# H-00488_-_Top.net
KiCad netlist of a schematic drawn in Altium Designer
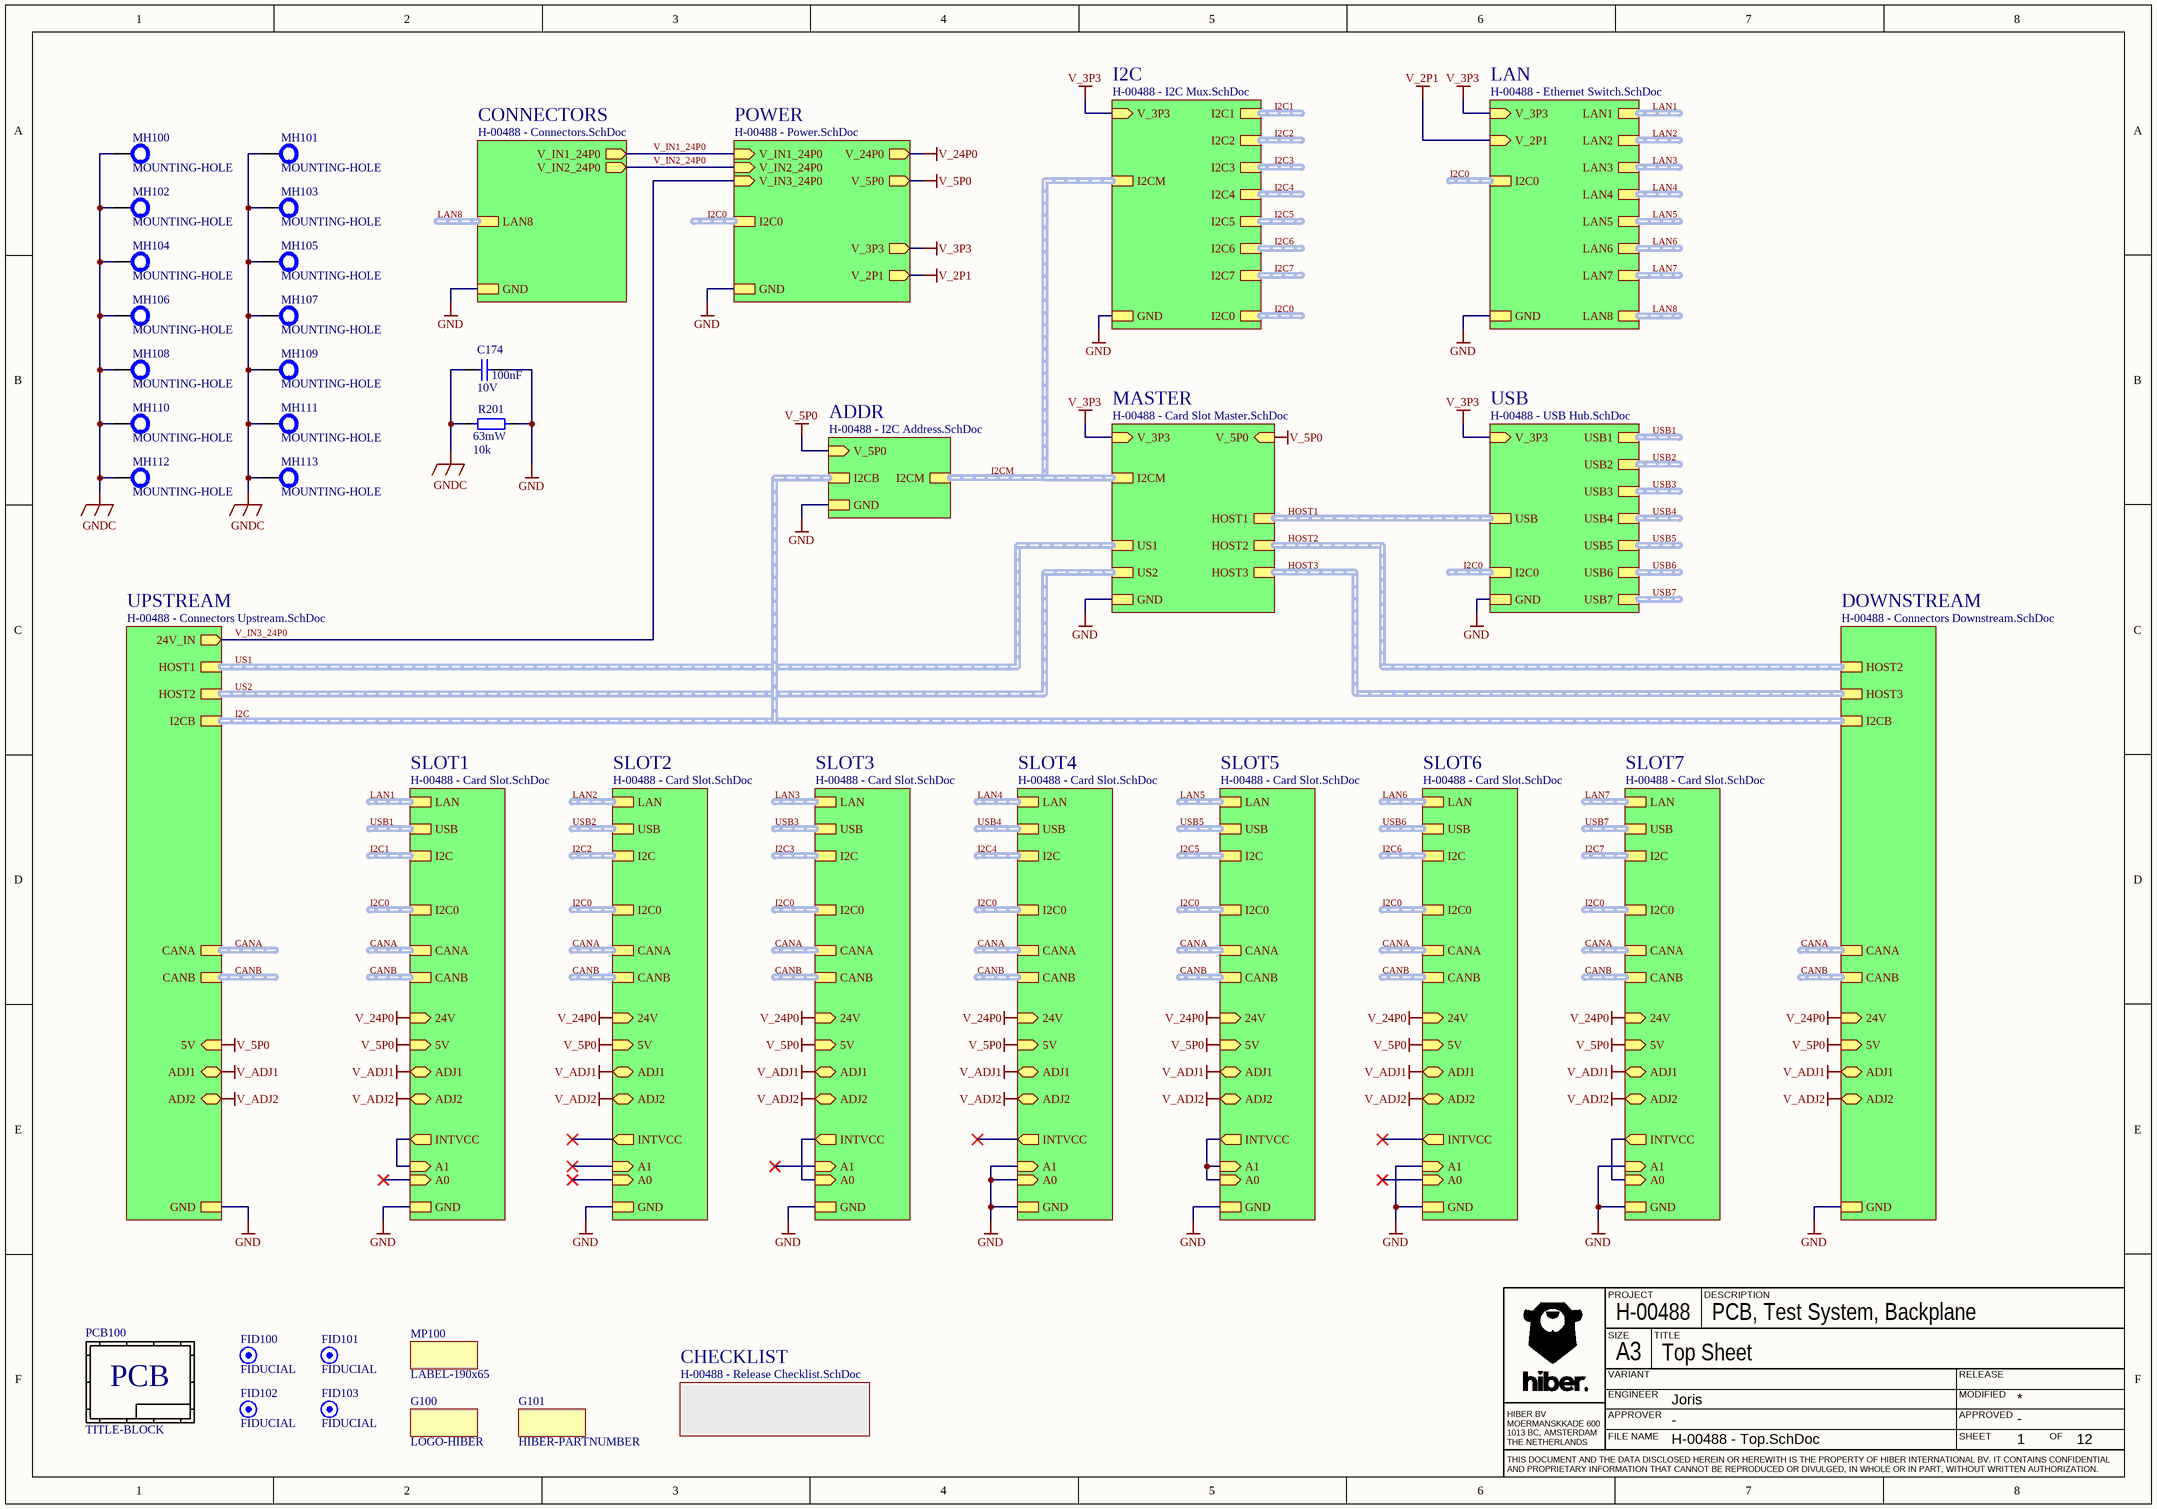
[diagram p0: H-00488 - Top.SchDoc]

(export (version "E")
  (design (tool "Eeschema 10.0.6"))
  (components
    (comp (ref "C174")
      (value "100nF")
      (footprint "CAPC100X50X55L30N")
      (description "CAP Standard 0402 (1005) 100,0nF 10V X7R (Standard)")
      (fields
        (field (name "RATED VOLTAGE") "10V")
        (field (name "TOLERANCE") "10%")
        (field (name "Comment") "C0402C104K8RACTU")
      )
      (libsource (lib "Hiber Vault") (part "CAPACITOR"))
    )
    (comp (ref "FID100")
      (value "FIDUCIAL")
      (footprint "FIDUCIAL_075X150")
      (description "Fiducial")
      (libsource (lib "Hiber Vault") (part "FIDUCIAL"))
    )
    (comp (ref "FID101")
      (value "FIDUCIAL")
      (footprint "FIDUCIAL_075X150")
      (description "Fiducial")
      (libsource (lib "Hiber Vault") (part "FIDUCIAL"))
    )
    (comp (ref "FID102")
      (value "FIDUCIAL")
      (footprint "FIDUCIAL_075X150")
      (description "Fiducial")
      (libsource (lib "Hiber Vault") (part "FIDUCIAL"))
    )
    (comp (ref "FID103")
      (value "FIDUCIAL")
      (footprint "FIDUCIAL_075X150")
      (description "Fiducial")
      (libsource (lib "Hiber Vault") (part "FIDUCIAL"))
    )
    (comp (ref "G100")
      (value "LOGO-HIBER")
      (footprint "HIBER_LOGO_COPPER_55x40")
      (description "Hiber Logo")
      (libsource (lib "Hiber Vault") (part "GRAPHIC"))
    )
    (comp (ref "G101")
      (value "HIBER-PARTNUMBER")
      (footprint "HIBER_PNSN_COPPER")
      (description "Hiber Fabrication Partnumber")
      (libsource (lib "Hiber") (part "GRAPHIC"))
    )
    (comp (ref "MH100")
      (value "MOUNTING-HOLE")
      (footprint "MTGP510H260V8H25")
      (description "Mounting Hole")
      (libsource (lib "Hiber Vault") (part "MOUNTING-HOLE-PLATED"))
    )
    (comp (ref "MH101")
      (value "MOUNTING-HOLE")
      (footprint "MTGP510H260V8H25")
      (description "Mounting Hole")
      (libsource (lib "Hiber Vault") (part "MOUNTING-HOLE-PLATED"))
    )
    (comp (ref "MH102")
      (value "MOUNTING-HOLE")
      (footprint "MTGP510H260V8H25")
      (description "Mounting Hole")
      (libsource (lib "Hiber Vault") (part "MOUNTING-HOLE-PLATED"))
    )
    (comp (ref "MH103")
      (value "MOUNTING-HOLE")
      (footprint "MTGP510H260V8H25")
      (description "Mounting Hole")
      (libsource (lib "Hiber Vault") (part "MOUNTING-HOLE-PLATED"))
    )
    (comp (ref "MH104")
      (value "MOUNTING-HOLE")
      (footprint "MTGP510H260V8H25")
      (description "Mounting Hole")
      (libsource (lib "Hiber Vault") (part "MOUNTING-HOLE-PLATED"))
    )
    (comp (ref "MH105")
      (value "MOUNTING-HOLE")
      (footprint "MTGP510H260V8H25")
      (description "Mounting Hole")
      (libsource (lib "Hiber Vault") (part "MOUNTING-HOLE-PLATED"))
    )
    (comp (ref "MH106")
      (value "MOUNTING-HOLE")
      (footprint "MTGP510H260V8H25")
      (description "Mounting Hole")
      (libsource (lib "Hiber Vault") (part "MOUNTING-HOLE-PLATED"))
    )
    (comp (ref "MH107")
      (value "MOUNTING-HOLE")
      (footprint "MTGP510H260V8H25")
      (description "Mounting Hole")
      (libsource (lib "Hiber Vault") (part "MOUNTING-HOLE-PLATED"))
    )
    (comp (ref "MH108")
      (value "MOUNTING-HOLE")
      (footprint "MTGP510H260V8H25")
      (description "Mounting Hole")
      (libsource (lib "Hiber Vault") (part "MOUNTING-HOLE-PLATED"))
    )
    (comp (ref "MH109")
      (value "MOUNTING-HOLE")
      (footprint "MTGP510H260V8H25")
      (description "Mounting Hole")
      (libsource (lib "Hiber Vault") (part "MOUNTING-HOLE-PLATED"))
    )
    (comp (ref "MH110")
      (value "MOUNTING-HOLE")
      (footprint "MTGP510H260V8H25")
      (description "Mounting Hole")
      (libsource (lib "Hiber Vault") (part "MOUNTING-HOLE-PLATED"))
    )
    (comp (ref "MH111")
      (value "MOUNTING-HOLE")
      (footprint "MTGP510H260V8H25")
      (description "Mounting Hole")
      (libsource (lib "Hiber Vault") (part "MOUNTING-HOLE-PLATED"))
    )
    (comp (ref "MH112")
      (value "MOUNTING-HOLE")
      (footprint "MTGP510H260V8H25")
      (description "Mounting Hole")
      (libsource (lib "Hiber Vault") (part "MOUNTING-HOLE-PLATED"))
    )
    (comp (ref "MH113")
      (value "MOUNTING-HOLE")
      (footprint "MTGP510H260V8H25")
      (description "Mounting Hole")
      (libsource (lib "Hiber Vault") (part "MOUNTING-HOLE-PLATED"))
    )
    (comp (ref "MP100")
      (value "LABEL-190x65")
      (footprint "LABEL_200X65_OVERLAY")
      (description "Label Placeholder 0.75\" x 0.25\" (Zebra 10015764)")
      (libsource (lib "Hiber") (part "MECHANICAL-PART"))
    )
    (comp (ref "PCB100")
      (value "TITLE-BLOCK")
      (footprint "TITLEBLOCK-A4")
      (description "Title Block and PCB BOM Line Item")
      (libsource (lib "Hiber") (part "TITLE-BLOCK"))
    )
    (comp (ref "R201")
      (value "10k")
      (footprint "RESC100X50X40L25N")
      (description "RES Standard Thick Film 0402 10K0 ±1% 0,063W")
      (fields
        (field (name "TOLERANCE") "1%")
        (field (name "RATED POWER") "63mW")
        (field (name "Comment") "CRCW040210K0FKED")
      )
      (libsource (lib "Hiber") (part "RESISTOR-2P"))
    )
  )
  (nets
    (net (code "80") (name "GND") (class "Default")
      (node (ref "C174") (pin "2") (pinfunction "2_2") (pintype "passive"))
      (node (ref "R201") (pin "2") (pinfunction "2_2") (pintype "passive"))
    )
    (net (code "81") (name "GNDC") (class "Default")
      (node (ref "C174") (pin "1") (pinfunction "1_1") (pintype "passive"))
      (node (ref "MH100") (pin "1") (pinfunction "1_1") (pintype "passive"))
      (node (ref "MH101") (pin "1") (pinfunction "1_1") (pintype "passive"))
      (node (ref "MH102") (pin "1") (pinfunction "1_1") (pintype "passive"))
      (node (ref "MH103") (pin "1") (pinfunction "1_1") (pintype "passive"))
      (node (ref "MH104") (pin "1") (pinfunction "1_1") (pintype "passive"))
      (node (ref "MH105") (pin "1") (pinfunction "1_1") (pintype "passive"))
      (node (ref "MH106") (pin "1") (pinfunction "1_1") (pintype "passive"))
      (node (ref "MH107") (pin "1") (pinfunction "1_1") (pintype "passive"))
      (node (ref "MH108") (pin "1") (pinfunction "1_1") (pintype "passive"))
      (node (ref "MH109") (pin "1") (pinfunction "1_1") (pintype "passive"))
      (node (ref "MH110") (pin "1") (pinfunction "1_1") (pintype "passive"))
      (node (ref "MH111") (pin "1") (pinfunction "1_1") (pintype "passive"))
      (node (ref "MH112") (pin "1") (pinfunction "1_1") (pintype "passive"))
      (node (ref "MH113") (pin "1") (pinfunction "1_1") (pintype "passive"))
      (node (ref "R201") (pin "1") (pinfunction "1_1") (pintype "passive"))
    )
  )
)
